# peripherals.net
KiCad netlist of a schematic drawn in Altium Designer
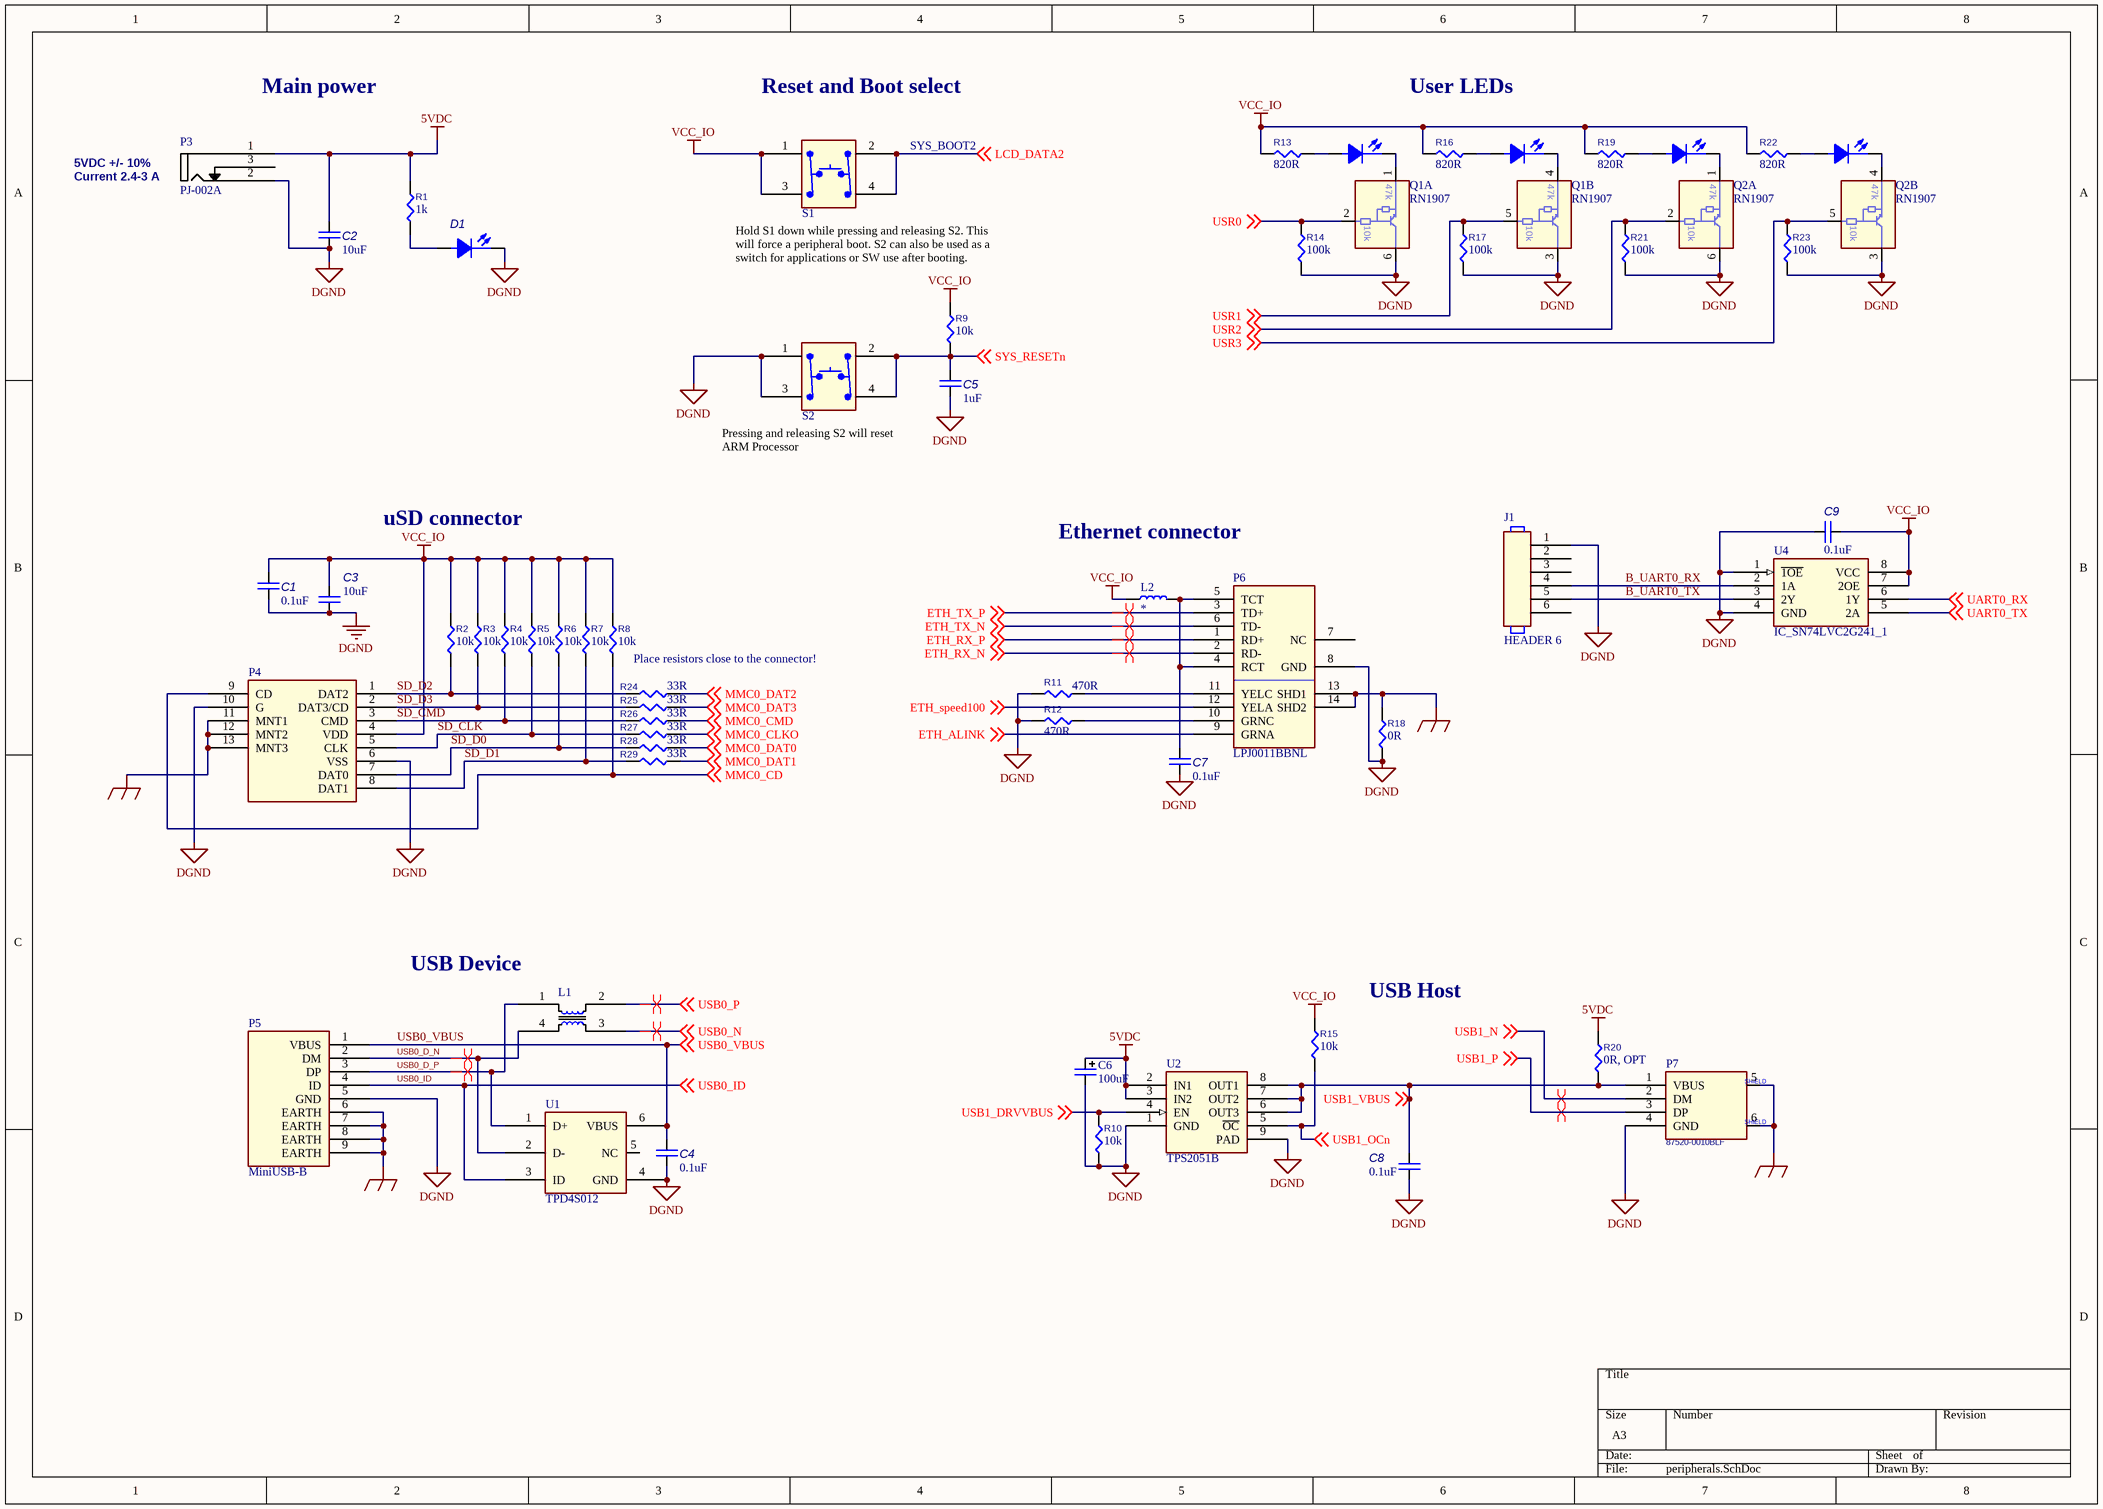
[diagram p0: peripherals.SchDoc]

(export (version "E")
  (design (tool "Eeschema 10.0.6"))
  (components
    (comp (ref "C1")
      (value "0.1uF")
      (footprint "CC1608-0603")
      (description "C0603")
      (libsource (lib "am335x-base") (part "C0603"))
    )
    (comp (ref "C2")
      (value "10uF")
      (footprint "CC2012-0805")
      (description "C0805")
      (libsource (lib "am335x-base") (part "C0805"))
    )
    (comp (ref "C3")
      (value "10uF")
      (footprint "CC2012-0805")
      (description "C0805")
      (libsource (lib "am335x-base") (part "C0805"))
    )
    (comp (ref "C4")
      (value "0.1uF")
      (footprint "CC1608-0603")
      (description "C0603")
      (libsource (lib "am335x-base") (part "C0603"))
    )
    (comp (ref "C5")
      (value "1uF")
      (footprint "CC1608-0603")
      (description "C0603")
      (libsource (lib "am335x-base") (part "C0603"))
    )
    (comp (ref "C6")
      (value "100uF")
      (footprint "Cap_C")
      (description "Tantalum Capacitor Case C")
      (fields (field (name "Comment") "Cap_C"))
      (libsource (lib "am335x-base") (part "Cap_C"))
    )
    (comp (ref "C7")
      (value "0.1uF")
      (footprint "CC1608-0603")
      (description "C0603")
      (libsource (lib "am335x-base") (part "C0603"))
    )
    (comp (ref "C8")
      (value "0.1uF")
      (footprint "CC1608-0603")
      (description "C0603")
      (libsource (lib "am335x-base") (part "C0603"))
    )
    (comp (ref "C9")
      (value "0.1uF")
      (footprint "CC1608-0603")
      (description "C0603")
      (libsource (lib "usomiq-base") (part "C0603"))
    )
    (comp (ref "D1")
      (value "LED0805")
      (footprint "LED0805")
      (description "LED 0805")
      (libsource (lib "am335x-base") (part "LED0805"))
    )
    (comp (ref "D2")
      (value "LED0805")
      (footprint "LED0805")
      (description "LED 0805")
      (libsource (lib "am335x-base") (part "LED0805"))
    )
    (comp (ref "D3")
      (value "LED0805")
      (footprint "LED0805")
      (description "LED 0805")
      (libsource (lib "am335x-base") (part "LED0805"))
    )
    (comp (ref "D4")
      (value "LED0805")
      (footprint "LED0805")
      (description "LED 0805")
      (libsource (lib "am335x-base") (part "LED0805"))
    )
    (comp (ref "D5")
      (value "LED0805")
      (footprint "LED0805")
      (description "LED 0805")
      (libsource (lib "am335x-base") (part "LED0805"))
    )
    (comp (ref "J1")
      (value "HEADER 6")
      (footprint "DIP6")
      (description "CONN HEADER 6POS, VERTICAL,  .100 STR TIN")
      (fields (field (name "MFR") "FCI"))
      (libsource (lib "usomiq-base") (part "HEADER 6"))
    )
    (comp (ref "L1")
      (value "DLW21H")
      (footprint "DLW21H")
      (description "Low profile wire-wound common choke coil")
      (fields (field (name "MANUFACTURER") "Murata"))
      (libsource (lib "am335x-base") (part "DLW21H"))
    )
    (comp (ref "L2")
      (value "BLM18A-FB")
      (footprint "CHIP0603")
      (description "Chip EMIFILr Inductor Type")
      (fields (field (name "MANUFACTURER") "Murata") (field (name "MAN P/N") "*"))
      (libsource (lib "am335x-base") (part "BLM18A-FB"))
    )
    (comp (ref "P3")
      (value "PJ-002A")
      (footprint "PJ-002A")
      (description "DC POWER JACK")
      (fields (field (name "MANUFACTURER") "CIU Inc"))
      (libsource (lib "omap") (part "PJ-002A"))
    )
    (comp (ref "P4")
      (value "~")
      (footprint "TFC08WP01F-A-R1K-H")
      (description "Connector for microSD™ Card (Push-push Type)")
      (fields (field (name "MFR") "AUK Contractors Co, LTD"))
      (libsource (lib "usomiq-base") (part "TFC08WP01F-R1K-H-CN"))
    )
    (comp (ref "P5")
      (value "MiniUSB-B")
      (footprint "MINI-USB-B5 SMT")
      (description "Mini USB Type B CONNECTOR")
      (fields (field (name "MFR") "Hirose"))
      (libsource (lib "usomiq-base") (part "MiniUSB-B"))
    )
    (comp (ref "P6")
      (value "CONN_RJ45_MAG_WE_0")
      (footprint "TRJ0011ABNL")
      (description "RJ-45 10/100 W/Magnetics")
      (fields (field (name "MFR") "Link PP") (field (name "P/N") "LPJ0011BBNL"))
      (libsource (lib "am335x-base") (part "CONN_RJ45_MAG_WE_0"))
    )
    (comp (ref "P7")
      (value "CONN_54819-0578_2")
      (footprint "USB2.5-2H4C")
      (description "USB Type A Connectors")
      (fields (field (name "P/N") "87520-0010BLF") (field (name "MFR") "FCI"))
      (libsource (lib "am335x-base") (part "CONN_54819-0578_2"))
    )
    (comp (ref "Q1")
      (value "RN1907")
      (footprint "SOT363-6L")
      (description "Transistor Silicon NPN")
      (fields (field (name "MFR") "Panasonic"))
      (libsource (lib "am335x-base") (part "RN1907"))
    )
    (comp (ref "Q2")
      (value "RN1907")
      (footprint "SOT363-6L")
      (description "Transistor Silicon NPN")
      (fields (field (name "MFR") "Panasonic"))
      (libsource (lib "am335x-base") (part "RN1907"))
    )
    (comp (ref "R1")
      (value "1k")
      (footprint "RESC1608X55N")
      (description "R0603")
      (libsource (lib "am335x-base") (part "R0603"))
    )
    (comp (ref "R2")
      (value "10k")
      (footprint "RESC1608X55N")
      (description "R0603")
      (libsource (lib "am335x-base") (part "R0603"))
    )
    (comp (ref "R3")
      (value "10k")
      (footprint "RESC1608X55N")
      (description "R0603")
      (libsource (lib "am335x-base") (part "R0603"))
    )
    (comp (ref "R4")
      (value "10k")
      (footprint "RESC1608X55N")
      (description "R0603")
      (libsource (lib "am335x-base") (part "R0603"))
    )
    (comp (ref "R5")
      (value "10k")
      (footprint "RESC1608X55N")
      (description "R0603")
      (libsource (lib "am335x-base") (part "R0603"))
    )
    (comp (ref "R6")
      (value "10k")
      (footprint "RESC1608X55N")
      (description "R0603")
      (libsource (lib "am335x-base") (part "R0603"))
    )
    (comp (ref "R7")
      (value "10k")
      (footprint "RESC1608X55N")
      (description "R0603")
      (libsource (lib "am335x-base") (part "R0603"))
    )
    (comp (ref "R8")
      (value "10k")
      (footprint "RESC1608X55N")
      (description "R0603")
      (libsource (lib "am335x-base") (part "R0603"))
    )
    (comp (ref "R9")
      (value "10k")
      (footprint "RESC1608X55N")
      (description "R0603")
      (libsource (lib "am335x-base") (part "R0603"))
    )
    (comp (ref "R10")
      (value "10k")
      (footprint "RESC1608X55N")
      (description "R0603")
      (libsource (lib "am335x-base") (part "R0603"))
    )
    (comp (ref "R11")
      (value "470R")
      (footprint "RESC1608X55N")
      (description "R0603")
      (libsource (lib "am335x-base") (part "R0603"))
    )
    (comp (ref "R12")
      (value "470R")
      (footprint "RESC1608X55N")
      (description "R0603")
      (libsource (lib "am335x-base") (part "R0603"))
    )
    (comp (ref "R13")
      (value "820R")
      (footprint "RESC1608X55N")
      (description "R0603")
      (libsource (lib "am335x-base") (part "R0603"))
    )
    (comp (ref "R14")
      (value "100k")
      (footprint "RESC1608X55N")
      (description "R0603")
      (libsource (lib "am335x-base") (part "R0603"))
    )
    (comp (ref "R15")
      (value "10k")
      (footprint "RESC1608X55N")
      (description "R0603")
      (libsource (lib "am335x-base") (part "R0603"))
    )
    (comp (ref "R16")
      (value "820R")
      (footprint "RESC1608X55N")
      (description "R0603")
      (libsource (lib "am335x-base") (part "R0603"))
    )
    (comp (ref "R17")
      (value "100k")
      (footprint "RESC1608X55N")
      (description "R0603")
      (libsource (lib "am335x-base") (part "R0603"))
    )
    (comp (ref "R18")
      (value "0R")
      (footprint "RESC1608X55N")
      (description "R0603")
      (libsource (lib "am335x-base") (part "R0603"))
    )
    (comp (ref "R19")
      (value "820R")
      (footprint "RESC1608X55N")
      (description "R0603")
      (libsource (lib "am335x-base") (part "R0603"))
    )
    (comp (ref "R20")
      (value "0R, OPT")
      (footprint "RESC1608X55N")
      (description "R0603")
      (libsource (lib "am335x-base") (part "R0603"))
    )
    (comp (ref "R21")
      (value "100k")
      (footprint "RESC1608X55N")
      (description "R0603")
      (libsource (lib "am335x-base") (part "R0603"))
    )
    (comp (ref "R22")
      (value "820R")
      (footprint "RESC1608X55N")
      (description "R0603")
      (libsource (lib "am335x-base") (part "R0603"))
    )
    (comp (ref "R23")
      (value "100k")
      (footprint "RESC1608X55N")
      (description "R0603")
      (libsource (lib "am335x-base") (part "R0603"))
    )
    (comp (ref "R24")
      (value "33R")
      (footprint "RESC1608X55N")
      (description "R0603")
      (libsource (lib "usomiq-base") (part "R0603"))
    )
    (comp (ref "R25")
      (value "33R")
      (footprint "RESC1608X55N")
      (description "R0603")
      (libsource (lib "usomiq-base") (part "R0603"))
    )
    (comp (ref "R26")
      (value "33R")
      (footprint "RESC1608X55N")
      (description "R0603")
      (libsource (lib "usomiq-base") (part "R0603"))
    )
    (comp (ref "R27")
      (value "33R")
      (footprint "RESC1608X55N")
      (description "R0603")
      (libsource (lib "usomiq-base") (part "R0603"))
    )
    (comp (ref "R28")
      (value "33R")
      (footprint "RESC1608X55N")
      (description "R0603")
      (libsource (lib "usomiq-base") (part "R0603"))
    )
    (comp (ref "R29")
      (value "33R")
      (footprint "RESC1608X55N")
      (description "R0603")
      (libsource (lib "usomiq-base") (part "R0603"))
    )
    (comp (ref "S1")
      (value "SW_KT11P2JM_2")
      (footprint "KMR231GLFS")
      (description "SMD button")
      (fields (field (name "MFR") "C&K Components"))
      (libsource (lib "usomiq-base") (part "SW_KT11P2JM_2"))
    )
    (comp (ref "S2")
      (value "SW_KT11P2JM_2")
      (footprint "KMR231GLFS")
      (description "SMD button")
      (fields (field (name "MFR") "C&K Components"))
      (libsource (lib "usomiq-base") (part "SW_KT11P2JM_2"))
    )
    (comp (ref "U1")
      (value "TPD4S012")
      (footprint "s-puson-n6")
      (description "4-Channel USB ESD Solution with Power Clamp")
      (fields (field (name "MFR") "TI"))
      (libsource (lib "usomiq-base") (part "TPD4S012"))
    )
    (comp (ref "U2")
      (value "TPS2051B")
      (footprint "R-PDSO-G8")
      (description "CURRENT-LIMITED, POWER-DISTRIBUTION SWITCHES")
      (fields (field (name "MFR") "TI"))
      (libsource (lib "usomiq-base") (part "TPS2051B"))
    )
    (comp (ref "U4")
      (value "IC_SN74LVC2G241_1")
      (footprint "SOP127P600-8N")
      (description "Dual Buffer/Driver With 3-State Outputs")
      (fields (field (name "MFR") "TI"))
      (libsource (lib "usomiq-base") (part "IC_SN74LVC2G241_1"))
    )
  )
  (nets
    (net (code "1") (name "/B_UART0_RX") (class "Default")
      (node (ref "J1") (pin "4") (pinfunction "4_4") (pintype "passive"))
      (node (ref "U4") (pin "2") (pinfunction "1A_2") (pintype "passive"))
    )
    (net (code "2") (name "/B_UART0_TX") (class "Default")
      (node (ref "J1") (pin "5") (pinfunction "5_5") (pintype "passive"))
      (node (ref "U4") (pin "3") (pinfunction "2Y_3") (pintype "passive"))
    )
    (net (code "3") (name "/SD_CLK") (class "Default")
      (node (ref "P4") (pin "5") (pinfunction "CLK_5") (pintype "passive"))
      (node (ref "R27") (pin "1") (pinfunction "1_1") (pintype "passive"))
      (node (ref "R5") (pin "1") (pinfunction "1_1") (pintype "passive"))
    )
    (net (code "4") (name "/SD_CMD") (class "Default")
      (node (ref "P4") (pin "3") (pinfunction "CMD_3") (pintype "passive"))
      (node (ref "R26") (pin "1") (pinfunction "1_1") (pintype "passive"))
      (node (ref "R4") (pin "1") (pinfunction "1_1") (pintype "passive"))
    )
    (net (code "5") (name "/SD_D0") (class "Default")
      (node (ref "P4") (pin "7") (pinfunction "DAT0_7") (pintype "passive"))
      (node (ref "R28") (pin "1") (pinfunction "1_1") (pintype "passive"))
      (node (ref "R6") (pin "1") (pinfunction "1_1") (pintype "passive"))
    )
    (net (code "6") (name "/SD_D1") (class "Default")
      (node (ref "P4") (pin "8") (pinfunction "DAT1_8") (pintype "passive"))
      (node (ref "R29") (pin "1") (pinfunction "1_1") (pintype "passive"))
      (node (ref "R7") (pin "1") (pinfunction "1_1") (pintype "passive"))
    )
    (net (code "7") (name "/SD_D2") (class "Default")
      (node (ref "P4") (pin "1") (pinfunction "DAT2_1") (pintype "passive"))
      (node (ref "R2") (pin "1") (pinfunction "1_1") (pintype "passive"))
      (node (ref "R24") (pin "1") (pinfunction "1_1") (pintype "passive"))
    )
    (net (code "8") (name "/SD_D3") (class "Default")
      (node (ref "P4") (pin "2") (pinfunction "DAT3/CD_2") (pintype "passive"))
      (node (ref "R25") (pin "1") (pinfunction "1_1") (pintype "passive"))
      (node (ref "R3") (pin "1") (pinfunction "1_1") (pintype "passive"))
    )
    (net (code "9") (name "/USB0_D_N") (class "Default")
      (node (ref "L1") (pin "4") (pinfunction "4_4") (pintype "passive"))
      (node (ref "P5") (pin "2") (pinfunction "DM_2") (pintype "passive"))
      (node (ref "U1") (pin "2") (pinfunction "D-_2") (pintype "passive"))
    )
    (net (code "10") (name "/USB0_D_P") (class "Default")
      (node (ref "L1") (pin "1") (pinfunction "1_1") (pintype "passive"))
      (node (ref "P5") (pin "3") (pinfunction "DP_3") (pintype "passive"))
      (node (ref "U1") (pin "1") (pinfunction "D+_1") (pintype "passive"))
    )
    (net (code "11") (name "5VDC") (class "Default")
      (node (ref "C2") (pin "2") (pinfunction "2_2") (pintype "passive"))
      (node (ref "C6") (pin "1") (pinfunction "1_1") (pintype "passive"))
      (node (ref "P3") (pin "1") (pinfunction "GND_1") (pintype "passive"))
      (node (ref "R1") (pin "2") (pinfunction "2_2") (pintype "passive"))
      (node (ref "R20") (pin "2") (pinfunction "2_2") (pintype "passive"))
      (node (ref "U2") (pin "2") (pinfunction "IN1_2") (pintype "power_in"))
      (node (ref "U2") (pin "3") (pinfunction "IN2_3") (pintype "power_in"))
    )
    (net (code "12") (name "DGND") (class "Default")
      (node (ref "C1") (pin "2") (pinfunction "2_2") (pintype "passive"))
      (node (ref "C2") (pin "1") (pinfunction "1_1") (pintype "passive"))
      (node (ref "C3") (pin "1") (pinfunction "1_1") (pintype "passive"))
      (node (ref "C4") (pin "2") (pinfunction "2_2") (pintype "passive"))
      (node (ref "C5") (pin "2") (pinfunction "2_2") (pintype "passive"))
      (node (ref "C6") (pin "2") (pinfunction "2_2") (pintype "passive"))
      (node (ref "C7") (pin "2") (pinfunction "2_2") (pintype "passive"))
      (node (ref "C8") (pin "1") (pinfunction "1_1") (pintype "passive"))
      (node (ref "C9") (pin "1") (pinfunction "1_1") (pintype "passive"))
      (node (ref "D1") (pin "2") (pinfunction "C_2") (pintype "passive"))
      (node (ref "J1") (pin "1") (pinfunction "1_1") (pintype "passive"))
      (node (ref "P3") (pin "2") (pinfunction "RIGHT_2") (pintype "passive"))
      (node (ref "P4") (pin "10") (pinfunction "G_10") (pintype "passive"))
      (node (ref "P4") (pin "6") (pinfunction "VSS_6") (pintype "power_in"))
      (node (ref "P5") (pin "5") (pinfunction "GND_5") (pintype "power_in"))
      (node (ref "P6") (pin "8") (pinfunction "GND_8") (pintype "passive"))
      (node (ref "P7") (pin "4") (pinfunction "GND_4") (pintype "passive"))
      (node (ref "Q1") (pin "3") (pinfunction "3_3") (pintype "passive"))
      (node (ref "Q1") (pin "6") (pinfunction "3_6") (pintype "passive"))
      (node (ref "Q2") (pin "3") (pinfunction "3_3") (pintype "passive"))
      (node (ref "Q2") (pin "6") (pinfunction "3_6") (pintype "passive"))
      (node (ref "R10") (pin "1") (pinfunction "1_1") (pintype "passive"))
      (node (ref "R11") (pin "1") (pinfunction "1_1") (pintype "passive"))
      (node (ref "R12") (pin "1") (pinfunction "1_1") (pintype "passive"))
      (node (ref "R14") (pin "1") (pinfunction "1_1") (pintype "passive"))
      (node (ref "R17") (pin "1") (pinfunction "1_1") (pintype "passive"))
      (node (ref "R18") (pin "1") (pinfunction "1_1") (pintype "passive"))
      (node (ref "R21") (pin "1") (pinfunction "1_1") (pintype "passive"))
      (node (ref "R23") (pin "1") (pinfunction "1_1") (pintype "passive"))
      (node (ref "S2") (pin "1") (pinfunction "A1_1") (pintype "passive"))
      (node (ref "S2") (pin "3") (pinfunction "A2_3") (pintype "passive"))
      (node (ref "U1") (pin "4") (pinfunction "GND_4") (pintype "power_in"))
      (node (ref "U2") (pin "1") (pinfunction "GND_1") (pintype "power_in"))
      (node (ref "U2") (pin "9") (pinfunction "PAD_9") (pintype "passive"))
      (node (ref "U4") (pin "1") (pinfunction "~{1OE}_1") (pintype "input"))
      (node (ref "U4") (pin "4") (pinfunction "GND_4") (pintype "power_in"))
    )
    (net (code "13") (name "EARTH") (class "Default")
      (node (ref "P4") (pin "11") (pinfunction "MNT1_11") (pintype "passive"))
      (node (ref "P4") (pin "12") (pinfunction "MNT2_12") (pintype "passive"))
      (node (ref "P4") (pin "13") (pinfunction "MNT3_13") (pintype "passive"))
      (node (ref "P5") (pin "6") (pinfunction "EARTH_6") (pintype "passive"))
      (node (ref "P5") (pin "7") (pinfunction "EARTH_7") (pintype "passive"))
      (node (ref "P5") (pin "8") (pinfunction "EARTH_8") (pintype "passive"))
      (node (ref "P5") (pin "9") (pinfunction "EARTH_9") (pintype "passive"))
      (node (ref "P6") (pin "13") (pinfunction "SHD1_13") (pintype "passive"))
      (node (ref "P6") (pin "14") (pinfunction "SHD2_14") (pintype "passive"))
      (node (ref "P7") (pin "5") (pinfunction "SHELD1_5") (pintype "passive"))
      (node (ref "P7") (pin "6") (pinfunction "PAD4_6") (pintype "passive"))
      (node (ref "R18") (pin "2") (pinfunction "2_2") (pintype "passive"))
    )
    (net (code "14") (name "ETH_ALINK") (class "Default")
      (node (ref "P6") (pin "9") (pinfunction "GRNA_9") (pintype "passive"))
    )
    (net (code "15") (name "ETH_RX_N") (class "Default")
      (node (ref "P6") (pin "2") (pinfunction "RD-_2") (pintype "passive"))
    )
    (net (code "16") (name "ETH_RX_P") (class "Default")
      (node (ref "P6") (pin "1") (pinfunction "RD+_1") (pintype "passive"))
    )
    (net (code "17") (name "ETH_TX_N") (class "Default")
      (node (ref "P6") (pin "6") (pinfunction "TD-_6") (pintype "passive"))
    )
    (net (code "18") (name "ETH_TX_P") (class "Default")
      (node (ref "P6") (pin "3") (pinfunction "TD+_3") (pintype "passive"))
    )
    (net (code "19") (name "ETH_speed100") (class "Default")
      (node (ref "P6") (pin "12") (pinfunction "YELA_12") (pintype "passive"))
    )
    (net (code "20") (name "LCD_DATA2") (class "Default")
      (node (ref "S1") (pin "2") (pinfunction "B1_2") (pintype "passive"))
      (node (ref "S1") (pin "4") (pinfunction "B2_4") (pintype "passive"))
    )
    (net (code "21") (name "MMC0_CD") (class "Default")
      (node (ref "P4") (pin "9") (pinfunction "CD_9") (pintype "passive"))
      (node (ref "R8") (pin "1") (pinfunction "1_1") (pintype "passive"))
    )
    (net (code "22") (name "MMC0_CLKO") (class "Default")
      (node (ref "R27") (pin "2") (pinfunction "2_2") (pintype "passive"))
    )
    (net (code "23") (name "MMC0_CMD") (class "Default")
      (node (ref "R26") (pin "2") (pinfunction "2_2") (pintype "passive"))
    )
    (net (code "24") (name "MMC0_DAT0") (class "Default")
      (node (ref "R28") (pin "2") (pinfunction "2_2") (pintype "passive"))
    )
    (net (code "25") (name "MMC0_DAT1") (class "Default")
      (node (ref "R29") (pin "2") (pinfunction "2_2") (pintype "passive"))
    )
    (net (code "26") (name "MMC0_DAT2") (class "Default")
      (node (ref "R24") (pin "2") (pinfunction "2_2") (pintype "passive"))
    )
    (net (code "27") (name "MMC0_DAT3") (class "Default")
      (node (ref "R25") (pin "2") (pinfunction "2_2") (pintype "passive"))
    )
    (net (code "28") (name "Net-(D1-A)") (class "Default")
      (node (ref "D1") (pin "1") (pinfunction "A_1") (pintype "passive"))
      (node (ref "R1") (pin "1") (pinfunction "1_1") (pintype "passive"))
    )
    (net (code "29") (name "Net-(D2-A)") (class "Default")
      (node (ref "D2") (pin "1") (pinfunction "A_1") (pintype "passive"))
      (node (ref "R13") (pin "1") (pinfunction "1_1") (pintype "passive"))
    )
    (net (code "30") (name "Net-(D2-C)") (class "Default")
      (node (ref "D2") (pin "2") (pinfunction "C_2") (pintype "passive"))
      (node (ref "Q1") (pin "1") (pinfunction "4_1") (pintype "passive"))
    )
    (net (code "31") (name "Net-(D3-A)") (class "Default")
      (node (ref "D3") (pin "1") (pinfunction "A_1") (pintype "passive"))
      (node (ref "R16") (pin "1") (pinfunction "1_1") (pintype "passive"))
    )
    (net (code "32") (name "Net-(D3-C)") (class "Default")
      (node (ref "D3") (pin "2") (pinfunction "C_2") (pintype "passive"))
      (node (ref "Q1") (pin "4") (pinfunction "4_4") (pintype "passive"))
    )
    (net (code "33") (name "Net-(D4-A)") (class "Default")
      (node (ref "D4") (pin "1") (pinfunction "A_1") (pintype "passive"))
      (node (ref "R19") (pin "1") (pinfunction "1_1") (pintype "passive"))
    )
    (net (code "34") (name "Net-(D4-C)") (class "Default")
      (node (ref "D4") (pin "2") (pinfunction "C_2") (pintype "passive"))
      (node (ref "Q2") (pin "1") (pinfunction "4_1") (pintype "passive"))
    )
    (net (code "35") (name "Net-(D5-A)") (class "Default")
      (node (ref "D5") (pin "1") (pinfunction "A_1") (pintype "passive"))
      (node (ref "R22") (pin "1") (pinfunction "1_1") (pintype "passive"))
    )
    (net (code "36") (name "Net-(D5-C)") (class "Default")
      (node (ref "D5") (pin "2") (pinfunction "C_2") (pintype "passive"))
      (node (ref "Q2") (pin "4") (pinfunction "4_4") (pintype "passive"))
    )
    (net (code "37") (name "Net-(P6-GRNC)") (class "Default")
      (node (ref "P6") (pin "10") (pinfunction "GRNC_10") (pintype "passive"))
      (node (ref "R12") (pin "2") (pinfunction "2_2") (pintype "passive"))
    )
    (net (code "38") (name "Net-(P6-RCT)") (class "Default")
      (node (ref "C7") (pin "1") (pinfunction "1_1") (pintype "passive"))
      (node (ref "L2") (pin "2") (pinfunction "2_2") (pintype "passive"))
      (node (ref "P6") (pin "4") (pinfunction "RCT_4") (pintype "passive"))
      (node (ref "P6") (pin "5") (pinfunction "TCT_5") (pintype "passive"))
    )
    (net (code "39") (name "Net-(P6-YELC)") (class "Default")
      (node (ref "P6") (pin "11") (pinfunction "YELC_11") (pintype "passive"))
      (node (ref "R11") (pin "2") (pinfunction "2_2") (pintype "passive"))
    )
    (net (code "40") (name "SYS_RESETn") (class "Default")
      (node (ref "C5") (pin "1") (pinfunction "1_1") (pintype "passive"))
      (node (ref "R9") (pin "1") (pinfunction "1_1") (pintype "passive"))
      (node (ref "S2") (pin "2") (pinfunction "B1_2") (pintype "passive"))
      (node (ref "S2") (pin "4") (pinfunction "B2_4") (pintype "passive"))
    )
    (net (code "41") (name "UART0_RX") (class "Default")
      (node (ref "U4") (pin "6") (pinfunction "1Y_6") (pintype "passive"))
    )
    (net (code "42") (name "UART0_TX") (class "Default")
      (node (ref "U4") (pin "5") (pinfunction "2A_5") (pintype "passive"))
    )
    (net (code "43") (name "USB0_ID") (class "Default")
      (node (ref "P5") (pin "4") (pinfunction "ID_4") (pintype "passive"))
      (node (ref "U1") (pin "3") (pinfunction "ID_3") (pintype "passive"))
    )
    (net (code "44") (name "USB0_N") (class "Default")
      (node (ref "L1") (pin "3") (pinfunction "3_3") (pintype "passive"))
    )
    (net (code "45") (name "USB0_P") (class "Default")
      (node (ref "L1") (pin "2") (pinfunction "2_2") (pintype "passive"))
    )
    (net (code "46") (name "USB0_VBUS") (class "Default")
      (node (ref "C4") (pin "1") (pinfunction "1_1") (pintype "passive"))
      (node (ref "P5") (pin "1") (pinfunction "VBUS_1") (pintype "power_in"))
      (node (ref "U1") (pin "6") (pinfunction "VBUS_6") (pintype "power_in"))
    )
    (net (code "47") (name "USB1_DRVVBUS") (class "Default")
      (node (ref "R10") (pin "2") (pinfunction "2_2") (pintype "passive"))
      (node (ref "U2") (pin "4") (pinfunction "EN_4") (pintype "input"))
    )
    (net (code "48") (name "USB1_N") (class "Default")
      (node (ref "P7") (pin "2") (pinfunction "DM_2") (pintype "passive"))
    )
    (net (code "49") (name "USB1_OCn") (class "Default")
      (node (ref "R15") (pin "1") (pinfunction "1_1") (pintype "passive"))
      (node (ref "U2") (pin "5") (pinfunction "~{OC}_5") (pintype "passive"))
    )
    (net (code "50") (name "USB1_P") (class "Default")
      (node (ref "P7") (pin "3") (pinfunction "DP_3") (pintype "passive"))
    )
    (net (code "51") (name "USB1_VBUS") (class "Default")
      (node (ref "C8") (pin "2") (pinfunction "2_2") (pintype "passive"))
      (node (ref "P7") (pin "1") (pinfunction "VBUS_1") (pintype "passive"))
      (node (ref "R20") (pin "1") (pinfunction "1_1") (pintype "passive"))
      (node (ref "U2") (pin "6") (pinfunction "OUT3_6") (pintype "power_in"))
      (node (ref "U2") (pin "7") (pinfunction "OUT2_7") (pintype "power_in"))
      (node (ref "U2") (pin "8") (pinfunction "OUT1_8") (pintype "power_in"))
    )
    (net (code "52") (name "USR0") (class "Default")
      (node (ref "Q1") (pin "2") (pinfunction "5_2") (pintype "passive"))
      (node (ref "R14") (pin "2") (pinfunction "2_2") (pintype "passive"))
    )
    (net (code "53") (name "USR1") (class "Default")
      (node (ref "Q1") (pin "5") (pinfunction "5_5") (pintype "passive"))
      (node (ref "R17") (pin "2") (pinfunction "2_2") (pintype "passive"))
    )
    (net (code "54") (name "USR2") (class "Default")
      (node (ref "Q2") (pin "2") (pinfunction "5_2") (pintype "passive"))
      (node (ref "R21") (pin "2") (pinfunction "2_2") (pintype "passive"))
    )
    (net (code "55") (name "USR3") (class "Default")
      (node (ref "Q2") (pin "5") (pinfunction "5_5") (pintype "passive"))
      (node (ref "R23") (pin "2") (pinfunction "2_2") (pintype "passive"))
    )
    (net (code "56") (name "VCC_IO") (class "Default")
      (node (ref "C1") (pin "1") (pinfunction "1_1") (pintype "passive"))
      (node (ref "C3") (pin "2") (pinfunction "2_2") (pintype "passive"))
      (node (ref "C9") (pin "2") (pinfunction "2_2") (pintype "passive"))
      (node (ref "L2") (pin "1") (pinfunction "1_1") (pintype "passive"))
      (node (ref "P4") (pin "4") (pinfunction "VDD_4") (pintype "power_in"))
      (node (ref "R13") (pin "2") (pinfunction "2_2") (pintype "passive"))
      (node (ref "R15") (pin "2") (pinfunction "2_2") (pintype "passive"))
      (node (ref "R16") (pin "2") (pinfunction "2_2") (pintype "passive"))
      (node (ref "R19") (pin "2") (pinfunction "2_2") (pintype "passive"))
      (node (ref "R2") (pin "2") (pinfunction "2_2") (pintype "passive"))
      (node (ref "R22") (pin "2") (pinfunction "2_2") (pintype "passive"))
      (node (ref "R3") (pin "2") (pinfunction "2_2") (pintype "passive"))
      (node (ref "R4") (pin "2") (pinfunction "2_2") (pintype "passive"))
      (node (ref "R5") (pin "2") (pinfunction "2_2") (pintype "passive"))
      (node (ref "R6") (pin "2") (pinfunction "2_2") (pintype "passive"))
      (node (ref "R7") (pin "2") (pinfunction "2_2") (pintype "passive"))
      (node (ref "R8") (pin "2") (pinfunction "2_2") (pintype "passive"))
      (node (ref "R9") (pin "2") (pinfunction "2_2") (pintype "passive"))
      (node (ref "S1") (pin "1") (pinfunction "A1_1") (pintype "passive"))
      (node (ref "S1") (pin "3") (pinfunction "A2_3") (pintype "passive"))
      (node (ref "U4") (pin "7") (pinfunction "2OE_7") (pintype "passive"))
      (node (ref "U4") (pin "8") (pinfunction "VCC_8") (pintype "power_in"))
    )
    (net (code "57") (name "unconnected-(J1-Pad2)") (class "Default")
      (node (ref "J1") (pin "2") (pinfunction "2_2") (pintype "passive"))
    )
    (net (code "58") (name "unconnected-(J1-Pad3)") (class "Default")
      (node (ref "J1") (pin "3") (pinfunction "3_3") (pintype "passive"))
    )
    (net (code "59") (name "unconnected-(J1-Pad6)") (class "Default")
      (node (ref "J1") (pin "6") (pinfunction "6_6") (pintype "passive"))
    )
    (net (code "60") (name "unconnected-(P3-LEFT-Pad3)") (class "Default")
      (node (ref "P3") (pin "3") (pinfunction "LEFT_3") (pintype "passive"))
    )
    (net (code "61") (name "unconnected-(P6-NC-Pad7)") (class "Default")
      (node (ref "P6") (pin "7") (pinfunction "NC_7") (pintype "passive"))
    )
    (net (code "62") (name "unconnected-(U1-NC-Pad5)") (class "Default")
      (node (ref "U1") (pin "5") (pinfunction "NC_5") (pintype "passive"))
    )
  )
)
